# PWR_P12V0.net
KiCad netlist of a schematic drawn in Altium Designer
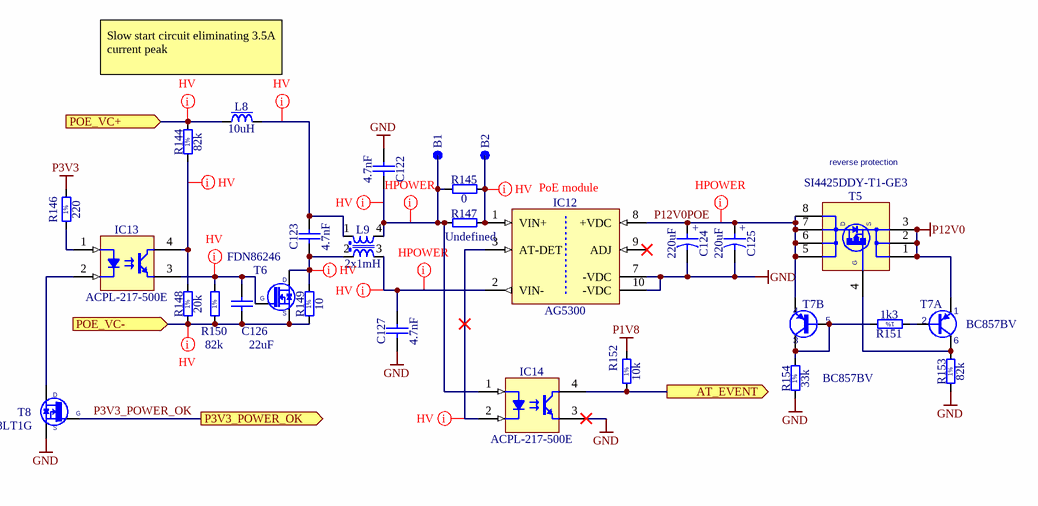
[diagram p0: PWR_P12V0.SchDoc]

(export (version "E")
  (design (tool "Eeschema 10.0.6"))
  (components
    (comp (ref "B1")
      (value "SMD Pad")
      (footprint "C100")
      (description "Through Hole Pad")
      (fields (field (name "PART NUMBER") "SMD_PAD_D1MM") (field (name "AUTHOR") "CERN DEM JLC"))
      (libsource (lib "Eletro-mechanical") (part "Single SMD Pad (Round)"))
    )
    (comp (ref "B2")
      (value "SMD Pad")
      (footprint "C100")
      (description "Through Hole Pad")
      (fields (field (name "PART NUMBER") "SMD_PAD_D1MM") (field (name "AUTHOR") "CERN DEM JLC"))
      (libsource (lib "Eletro-mechanical") (part "Single SMD Pad (Round)"))
    )
    (comp (ref "C122")
      (value "4.7nF")
      (footprint "CAPC3216X140N")
      (description "Non-polarised capacitor")
      (fields
        (field (name "PART NUMBER") "CC1206_4.7NF_500V_10%_X7R")
        (field (name "VOLTAGE") "500V")
        (field (name "AUTHOR") "GK")
      )
      (libsource (lib "LIBRARY_SCH") (part "CAP_SMD_1206_4.7n_500V"))
    )
    (comp (ref "C123")
      (value "4.7nF")
      (footprint "CAPC3216X140N")
      (description "Non-polarised capacitor")
      (fields
        (field (name "PART NUMBER") "CC1206_4.7NF_500V_10%_X7R")
        (field (name "VOLTAGE") "500V")
        (field (name "AUTHOR") "GK")
      )
      (libsource (lib "LIBRARY_SCH") (part "CAP_SMD_1206_4.7n_500V"))
    )
    (comp (ref "C124")
      (value "220uF")
      (footprint "CAPAE830X620N")
      (description "Polarised capacitor")
      (fields
        (field (name "PART NUMBER") "CAE830-620_220UF_16V_20%")
        (field (name "VOLTAGE") "16V")
        (field (name "AUTHOR") "CERN DEM JLC")
      )
      (libsource (lib "Capacitors") (part "Capacitor - polarized"))
    )
    (comp (ref "C125")
      (value "220uF")
      (footprint "CAPAE830X620N")
      (description "Polarised capacitor")
      (fields
        (field (name "PART NUMBER") "CAE830-620_220UF_16V_20%")
        (field (name "VOLTAGE") "16V")
        (field (name "AUTHOR") "CERN DEM JLC")
      )
      (libsource (lib "Capacitors") (part "Capacitor - polarized"))
    )
    (comp (ref "C126")
      (value "22uF")
      (footprint "CAPC2012X135N")
      (description "Non-polarised capacitor")
      (fields
        (field (name "PART NUMBER") "CC0805_22UF_16V_10%_X5R")
        (field (name "VOLTAGE") "16V")
        (field (name "AUTHOR") "CERN DEM JLC")
      )
      (libsource (lib "Capacitors") (part "Capacitor - non polarized"))
    )
    (comp (ref "C127")
      (value "4.7nF")
      (footprint "CAPC3216X140N")
      (description "Non-polarised capacitor")
      (fields
        (field (name "PART NUMBER") "CC1206_4.7NF_500V_10%_X7R")
        (field (name "VOLTAGE") "500V")
        (field (name "AUTHOR") "GK")
      )
      (libsource (lib "LIBRARY_SCH") (part "CAP_SMD_1206_4.7n_500V"))
    )
    (comp (ref "IC12")
      (value "AG5300")
      (footprint "SILVERTEL_AG5300")
      (description "Power-over-Ethernet Plus (POE+) Module")
      (fields (field (name "MANUFACTURER") "SILVERTEL") (field (name "AUTHOR") "CERN DEM JLC"))
      (libsource (lib "ICs And Semiconductors") (part "AG5300"))
    )
    (comp (ref "IC13")
      (value "ACPL-217-500E")
      (footprint "SOIC127P700X242-4N")
      (description "Single Optocoupler")
      (fields (field (name "MANUFACTURER") "AVAGO TECHNOLOGIES") (field (name "AUTHOR") "CERN DEM JLC"))
      (libsource (lib "ICs And Semiconductors") (part "Optocoupler Type7"))
    )
    (comp (ref "IC14")
      (value "ACPL-217-500E")
      (footprint "SOIC127P700X242-4N")
      (description "Single Optocoupler")
      (fields (field (name "MANUFACTURER") "AVAGO TECHNOLOGIES") (field (name "AUTHOR") "CERN DEM JLC"))
      (libsource (lib "ICs And Semiconductors") (part "Optocoupler Type7"))
    )
    (comp (ref "L8")
      (value "10uH")
      (footprint "IND_MURATA-PS_8400")
      (description "Inductor With Core")
      (fields
        (field (name "PART NUMBER") "IND_10UH_10%_MURATA-PS_8400")
        (field (name "POWER") "950mA")
        (field (name "AUTHOR") "CERN DEM JLC")
      )
      (libsource (lib "Inductors & Transformers") (part "Inductor With Magnetic core"))
    )
    (comp (ref "L9")
      (value "2x1mH")
      (footprint "IND_WURTH_WE-SL2")
      (description "Inductor Common Mode")
      (fields
        (field (name "PART NUMBER") "IND_1MH_50%_WURTH_WE-SL2-744222")
        (field (name "POWER") "800mA")
        (field (name "AUTHOR") "CERN DEM JLC")
      )
      (libsource (lib "Inductors & Transformers") (part "Inductor Common Mode 1Dot-4 2Dot-3"))
    )
    (comp (ref "R144")
      (value "82k")
      (footprint "RESC1608X55N")
      (description "Resistor - 1%")
      (fields
        (field (name "PART NUMBER") "R0603_82K_1%_0.1W_100PPM")
        (field (name "POWER") "0.1W")
        (field (name "AUTHOR") "CERN DEM JLC")
      )
      (libsource (lib "Resistors") (part "Resistor - 1%"))
    )
    (comp (ref "R145")
      (value "0")
      (footprint "RESC1005X40N")
      (description "Resistor")
      (fields
        (field (name "PART NUMBER") "R0402_0R_JUMPER")
        (field (name "MANUFACTURER") "GENERIC")
        (field (name "AUTHOR") "CERN DEM JLC")
      )
      (libsource (lib "Resistors") (part "Resistor"))
    )
    (comp (ref "R146")
      (value "220")
      (footprint "RESC1608X55N")
      (description "Resistor - 1%")
      (fields
        (field (name "PART NUMBER") "R0603_220R_1%_0.1W_100PPM")
        (field (name "POWER") "0.1W")
        (field (name "AUTHOR") "CERN DEM JLC")
      )
      (libsource (lib "Resistors") (part "Resistor - 1%"))
    )
    (comp (ref "R147")
      (value "Undefined")
      (footprint "RESC2012X60N")
      (description "Resistor")
      (fields (field (name "PART NUMBER") "R0805_NO-VALUE") (field (name "AUTHOR") "CERN DEM JLC"))
      (libsource (lib "Resistors") (part "Resistor"))
    )
    (comp (ref "R148")
      (value "20k")
      (footprint "RESC1005X40N")
      (description "Resistor - 1%")
      (fields
        (field (name "PART NUMBER") "R0402_20K_1%_0.0625W_100PPM")
        (field (name "POWER") "0.0625W")
        (field (name "AUTHOR") "CERN DEM JLC")
      )
      (libsource (lib "Resistors") (part "Resistor - 1%"))
    )
    (comp (ref "R149")
      (value "10")
      (footprint "RESC1005X40N")
      (description "Resistor - 1%")
      (fields
        (field (name "PART NUMBER") "R0402_10R_1%_0.0625W_200PPM")
        (field (name "POWER") "0.0625W")
        (field (name "AUTHOR") "CERN DEM JLC")
      )
      (libsource (lib "Resistors") (part "Resistor - 1%"))
    )
    (comp (ref "R150")
      (value "82k")
      (footprint "RESC1608X55N")
      (description "Resistor - 1%")
      (fields
        (field (name "PART NUMBER") "R0603_82K_1%_0.1W_100PPM")
        (field (name "POWER") "0.1W")
        (field (name "AUTHOR") "CERN DEM JLC")
      )
      (libsource (lib "Resistors") (part "Resistor - 1%"))
    )
    (comp (ref "R151")
      (value "1k3")
      (footprint "RESC1608X55N")
      (description "Resistor - 1%")
      (fields
        (field (name "PART NUMBER") "R0603_1K3_1%_0.1W_100PPM")
        (field (name "POWER") "0.1W")
        (field (name "AUTHOR") "CERN DEM JLC")
      )
      (libsource (lib "Resistors") (part "Resistor - 1%"))
    )
    (comp (ref "R152")
      (value "10k")
      (footprint "RESC1005X40N")
      (description "Resistor - 1%")
      (fields
        (field (name "PART NUMBER") "R0402_10K_1%_0.0625W_100PPM")
        (field (name "POWER") "0.0625W")
        (field (name "AUTHOR") "CERN DEM JLC")
      )
      (libsource (lib "Resistors") (part "Resistor - 1%"))
    )
    (comp (ref "R153")
      (value "82k")
      (footprint "RESC1608X55N")
      (description "Resistor - 1%")
      (fields
        (field (name "PART NUMBER") "R0603_82K_1%_0.1W_100PPM")
        (field (name "POWER") "0.1W")
        (field (name "AUTHOR") "CERN DEM JLC")
      )
      (libsource (lib "Resistors") (part "Resistor - 1%"))
    )
    (comp (ref "R154")
      (value "33k")
      (footprint "RESC1005X40N")
      (description "Resistor - 1%")
      (fields
        (field (name "PART NUMBER") "R0402_33K_1%_0.0625W_100PPM")
        (field (name "POWER") "0.0625W")
        (field (name "AUTHOR") "CERN DEM JLC")
      )
      (libsource (lib "Resistors") (part "Resistor - 1%"))
    )
    (comp (ref "T5")
      (value "SI4425DDY-T1-GE3")
      (footprint "SOIC127P600X175-8N")
      (description "-30V -19.7A P-Channel MOSFET")
      (fields (field (name "MANUFACTURER") "VISHAY SILICONIX") (field (name "AUTHOR") "CERN DEM MR"))
      (libsource (lib "ICs And Semiconductors") (part "SI4425DDY"))
    )
    (comp (ref "T6")
      (value "FDN86246")
      (footprint "SOT95P237X112-3N")
      (description "N-CHANNEL MOSFET WITH DIODE")
      (fields (field (name "MANUFACTURER") "ON SEMICONDUCTOR") (field (name "AUTHOR") "CERN DEM BC"))
      (libsource (lib "ICs And Semiconductors") (part "N-MOSFET-D 1G 2S 3D"))
    )
    (comp (ref "T7")
      (value "BC857BV")
      (footprint "SOTFL50P160X60-6N")
      (description "45V, 100mA PNP General Purpose Double Transistor")
      (fields (field (name "MANUFACTURER") "NXP SEMICONDUCTORS") (field (name "AUTHOR") "CERN DEM JLC"))
      (libsource (lib "ICs And Semiconductors") (part "BC857BV"))
    )
    (comp (ref "T8")
      (value "BSS138LT1G")
      (footprint "SOT95P240X110-3N")
      (description "N-CHANNEL MOSFET WITH DIODE")
      (fields (field (name "MANUFACTURER") "ON SEMICONDUCTOR") (field (name "AUTHOR") "CERN DEM JLC"))
      (libsource (lib "") (part "N-MOSFET-D 1G 2S 3D_1"))
    )
  )
  (nets
    (net (code "1") (name "/AT_EVENT") (class "Default")
      (node (ref "IC14") (pin "4") (pinfunction "C_4") (pintype "open_collector"))
      (node (ref "R152") (pin "1") (pinfunction "1_1") (pintype "passive"))
    )
    (net (code "2") (name "/P3V3_POWER_OK") (class "Default")
      (node (ref "T8") (pin "1") (pinfunction "G_1") (pintype "passive"))
    )
    (net (code "3") (name "/P12V0POE") (class "Default")
      (node (ref "C124") (pin "1") (pinfunction "1_1") (pintype "passive"))
      (node (ref "C125") (pin "1") (pinfunction "1_1") (pintype "passive"))
      (node (ref "IC12") (pin "8") (pinfunction "+VDC_8") (pintype "input"))
      (node (ref "T5") (pin "5") (pinfunction "D_5") (pintype "passive"))
      (node (ref "T5") (pin "6") (pinfunction "D_6") (pintype "passive"))
      (node (ref "T5") (pin "7") (pinfunction "D_7") (pintype "passive"))
      (node (ref "T5") (pin "8") (pinfunction "D_8") (pintype "passive"))
      (node (ref "T7") (pin "4") (pinfunction "E_4") (pintype "passive"))
    )
    (net (code "4") (name "/POE_VC+") (class "Default")
      (node (ref "L8") (pin "1") (pinfunction "1_1") (pintype "passive"))
      (node (ref "R144") (pin "2") (pinfunction "2_2") (pintype "passive"))
    )
    (net (code "5") (name "/POE_VC-") (class "Default")
      (node (ref "C126") (pin "1") (pinfunction "1_1") (pintype "passive"))
      (node (ref "R148") (pin "1") (pinfunction "1_1") (pintype "passive"))
      (node (ref "R149") (pin "1") (pinfunction "1_1") (pintype "passive"))
      (node (ref "R150") (pin "1") (pinfunction "1_1") (pintype "passive"))
      (node (ref "T6") (pin "2") (pinfunction "S_2") (pintype "passive"))
    )
    (net (code "6") (name "GND") (class "Default")
      (node (ref "C122") (pin "1") (pinfunction "1_1") (pintype "passive"))
      (node (ref "C124") (pin "2") (pinfunction "2_2") (pintype "passive"))
      (node (ref "C125") (pin "2") (pinfunction "2_2") (pintype "passive"))
      (node (ref "C127") (pin "1") (pinfunction "1_1") (pintype "passive"))
      (node (ref "IC12") (pin "10") (pinfunction "-VDC_10") (pintype "power_in"))
      (node (ref "IC12") (pin "7") (pinfunction "-VDC_7") (pintype "power_in"))
      (node (ref "IC14") (pin "3") (pinfunction "E_3") (pintype "open_emitter"))
      (node (ref "R153") (pin "1") (pinfunction "1_1") (pintype "passive"))
      (node (ref "R154") (pin "1") (pinfunction "1_1") (pintype "passive"))
      (node (ref "T8") (pin "2") (pinfunction "S_2") (pintype "passive"))
    )
    (net (code "7") (name "Net-(C123-Pad2)") (class "Default")
      (node (ref "C123") (pin "2") (pinfunction "2_2") (pintype "passive"))
      (node (ref "L8") (pin "2") (pinfunction "2_2") (pintype "passive"))
      (node (ref "L9") (pin "1") (pinfunction "1_1") (pintype "passive"))
    )
    (net (code "8") (name "Net-(IC12-AT-DET)") (class "Default")
      (node (ref "IC12") (pin "3") (pinfunction "AT-DET_3") (pintype "input"))
      (node (ref "IC14") (pin "2") (pinfunction "C_2") (pintype "input"))
    )
    (net (code "9") (name "Net-(IC12-VIN+)") (class "Default")
      (node (ref "B2") (pin "1") (pinfunction "1_1") (pintype "bidirectional"))
      (node (ref "IC12") (pin "1") (pinfunction "VIN+_1") (pintype "input"))
      (node (ref "R145") (pin "2") (pinfunction "2_2") (pintype "passive"))
      (node (ref "R147") (pin "2") (pinfunction "2_2") (pintype "passive"))
    )
    (net (code "10") (name "Net-(IC12-VIN-)") (class "Default")
      (node (ref "C127") (pin "2") (pinfunction "2_2") (pintype "passive"))
      (node (ref "IC12") (pin "2") (pinfunction "VIN-_2") (pintype "output"))
      (node (ref "L9") (pin "3") (pinfunction "3_3") (pintype "passive"))
    )
    (net (code "11") (name "Net-(IC13-A)") (class "Default")
      (node (ref "IC13") (pin "1") (pinfunction "A_1") (pintype "input"))
      (node (ref "R146") (pin "1") (pinfunction "1_1") (pintype "passive"))
    )
    (net (code "12") (name "Net-(IC13-C-Pad4)") (class "Default")
      (node (ref "IC13") (pin "4") (pinfunction "C_4") (pintype "open_collector"))
      (node (ref "R144") (pin "1") (pinfunction "1_1") (pintype "passive"))
      (node (ref "R148") (pin "2") (pinfunction "2_2") (pintype "passive"))
    )
    (net (code "13") (name "Net-(IC13-E)") (class "Default")
      (node (ref "C126") (pin "2") (pinfunction "2_2") (pintype "passive"))
      (node (ref "IC13") (pin "3") (pinfunction "E_3") (pintype "open_emitter"))
      (node (ref "R150") (pin "2") (pinfunction "2_2") (pintype "passive"))
      (node (ref "T6") (pin "1") (pinfunction "G_1") (pintype "passive"))
    )
    (net (code "14") (name "Net-(IC14-A)") (class "Default")
      (node (ref "B1") (pin "1") (pinfunction "1_1") (pintype "bidirectional"))
      (node (ref "C122") (pin "2") (pinfunction "2_2") (pintype "passive"))
      (node (ref "IC14") (pin "1") (pinfunction "A_1") (pintype "input"))
      (node (ref "L9") (pin "4") (pinfunction "4_4") (pintype "passive"))
      (node (ref "R145") (pin "1") (pinfunction "1_1") (pintype "passive"))
      (node (ref "R147") (pin "1") (pinfunction "1_1") (pintype "passive"))
    )
    (net (code "15") (name "Net-(T6-D)") (class "Default")
      (node (ref "C123") (pin "1") (pinfunction "1_1") (pintype "passive"))
      (node (ref "L9") (pin "2") (pinfunction "2_2") (pintype "passive"))
      (node (ref "R149") (pin "2") (pinfunction "2_2") (pintype "passive"))
      (node (ref "T6") (pin "3") (pinfunction "D_3") (pintype "passive"))
    )
    (net (code "16") (name "Net-(T7A-B)") (class "Default")
      (node (ref "R151") (pin "1") (pinfunction "1_1") (pintype "passive"))
      (node (ref "T7") (pin "2") (pinfunction "B_2") (pintype "passive"))
    )
    (net (code "17") (name "Net-(T7A-C)") (class "Default")
      (node (ref "R153") (pin "2") (pinfunction "2_2") (pintype "passive"))
      (node (ref "T5") (pin "4") (pinfunction "S_4") (pintype "passive"))
      (node (ref "T7") (pin "6") (pinfunction "C_6") (pintype "passive"))
    )
    (net (code "18") (name "Net-(T7B-B)") (class "Default")
      (node (ref "R151") (pin "2") (pinfunction "2_2") (pintype "passive"))
      (node (ref "R154") (pin "2") (pinfunction "2_2") (pintype "passive"))
      (node (ref "T7") (pin "3") (pinfunction "C_3") (pintype "passive"))
      (node (ref "T7") (pin "5") (pinfunction "B_5") (pintype "passive"))
    )
    (net (code "19") (name "Net-(T8-D)") (class "Default")
      (node (ref "IC13") (pin "2") (pinfunction "C_2") (pintype "input"))
      (node (ref "T8") (pin "3") (pinfunction "D_3") (pintype "passive"))
    )
    (net (code "20") (name "P1V8") (class "Default")
      (node (ref "R152") (pin "2") (pinfunction "2_2") (pintype "passive"))
    )
    (net (code "21") (name "P3V3") (class "Default")
      (node (ref "R146") (pin "2") (pinfunction "2_2") (pintype "passive"))
    )
    (net (code "22") (name "P12V0") (class "Default")
      (node (ref "T5") (pin "1") (pinfunction "S_1") (pintype "passive"))
      (node (ref "T5") (pin "2") (pinfunction "S_2") (pintype "passive"))
      (node (ref "T5") (pin "3") (pinfunction "S_3") (pintype "passive"))
      (node (ref "T7") (pin "1") (pinfunction "E_1") (pintype "passive"))
    )
    (net (code "23") (name "unconnected-(IC12-ADJ-Pad9)") (class "Default")
      (node (ref "IC12") (pin "9") (pinfunction "ADJ_9") (pintype "input+no_connect"))
    )
  )
)
